# relay_wired.net
KiCad netlist of a schematic drawn in EAGLE
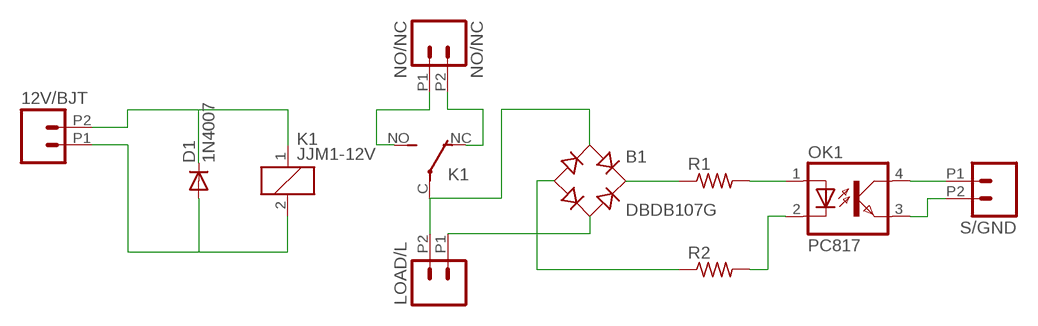
[diagram p0: schematic, sheet 1]

(export (version "E")
  (design (tool "Eeschema 10.0.6"))
  (components
    (comp (ref "12V/BJT")
      (value "M022.54MM_SCREWTERM")
      (footprint "eagle-import:1X02_2.54_SCREWTERM")
      (libsource (lib "eagle-import") (part "M022.54MM_SCREWTERM"))
    )
    (comp (ref "B1")
      (value "DBDB107G")
      (footprint "eagle-import:DB")
      (libsource (lib "eagle-import") (part "DB?GDB107"))
    )
    (comp (ref "D1")
      (value "1N4007")
      (footprint "eagle-import:DO41-10")
      (libsource (lib "eagle-import") (part "1N4004"))
    )
    (comp (ref "K1")
      (value "JJM1-12V")
      (footprint "eagle-import:JJM1C")
      (fields (field (name "MF") "AROMAT/ MATSUSHITA"))
      (libsource (lib "eagle-import") (part "JJM1-12V"))
    )
    (comp (ref "LOAD/L")
      (value "M022.54MM_SCREWTERM")
      (footprint "eagle-import:1X02_2.54_SCREWTERM")
      (libsource (lib "eagle-import") (part "M022.54MM_SCREWTERM"))
    )
    (comp (ref "NO/NC")
      (value "NO/NC")
      (footprint "eagle-import:1X02_2.54_SCREWTERM")
      (libsource (lib "eagle-import") (part "M022.54MM_SCREWTERM"))
    )
    (comp (ref "OK1")
      (value "PC817")
      (footprint "eagle-import:DIL04")
      (fields (field (name "MPN") "PC817X4J000F"))
      (libsource (lib "eagle-import") (part "PC817"))
    )
    (comp (ref "R1")
      (value "R-US_0207/10")
      (footprint "eagle-import:0207_10")
      (libsource (lib "eagle-import") (part "R-US_0207/10"))
    )
    (comp (ref "R2")
      (value "R-US_0207/10")
      (footprint "eagle-import:0207_10")
      (libsource (lib "eagle-import") (part "R-US_0207/10"))
    )
    (comp (ref "S/GND")
      (value "M022.54MM_SCREWTERM")
      (footprint "eagle-import:1X02_2.54_SCREWTERM")
      (libsource (lib "eagle-import") (part "M022.54MM_SCREWTERM"))
    )
  )
  (nets
    (net (code "1") (name "Net-(12V/BJT-1)") (class "Default")
      (node (ref "12V/BJT") (pin "P1") (pinfunction "1_P1") (pintype "passive"))
      (node (ref "D1") (pin "A") (pinfunction "A_A") (pintype "passive"))
      (node (ref "K1") (pin "2") (pinfunction "2_2") (pintype "passive"))
    )
    (net (code "2") (name "Net-(12V/BJT-2)") (class "Default")
      (node (ref "12V/BJT") (pin "P2") (pinfunction "2_P2") (pintype "passive"))
      (node (ref "D1") (pin "C") (pinfunction "C_C") (pintype "passive"))
      (node (ref "K1") (pin "1") (pinfunction "1_1") (pintype "passive"))
    )
    (net (code "3") (name "Net-(B1-Pad+)") (class "Default")
      (node (ref "B1") (pin "+") (pinfunction "+_+") (pintype "passive"))
      (node (ref "R1") (pin "1") (pinfunction "1_1") (pintype "passive"))
    )
    (net (code "4") (name "Net-(B1-Pad-)") (class "Default")
      (node (ref "B1") (pin "-") (pinfunction "-_-") (pintype "passive"))
      (node (ref "R2") (pin "1") (pinfunction "1_1") (pintype "passive"))
    )
    (net (code "5") (name "Net-(K1B-O)") (class "Default")
      (node (ref "K1") (pin "NC") (pinfunction "O_NC") (pintype "passive"))
      (node (ref "NO/NC") (pin "P2") (pinfunction "2_P2") (pintype "passive"))
    )
    (net (code "6") (name "Net-(K1B-P)") (class "Default")
      (node (ref "B1") (pin "AC1") (pinfunction "AC1_AC1") (pintype "passive"))
      (node (ref "K1") (pin "C") (pinfunction "P_C") (pintype "passive"))
      (node (ref "LOAD/L") (pin "P2") (pinfunction "2_P2") (pintype "passive"))
    )
    (net (code "7") (name "Net-(K1B-S)") (class "Default")
      (node (ref "K1") (pin "NO") (pinfunction "S_NO") (pintype "passive"))
      (node (ref "NO/NC") (pin "P1") (pinfunction "1_P1") (pintype "passive"))
    )
    (net (code "8") (name "Net-(LOAD/L-1)") (class "Default")
      (node (ref "B1") (pin "AC2") (pinfunction "AC2_AC2") (pintype "passive"))
      (node (ref "LOAD/L") (pin "P1") (pinfunction "1_P1") (pintype "passive"))
    )
    (net (code "9") (name "Net-(OK1-A)") (class "Default")
      (node (ref "OK1") (pin "1") (pinfunction "A_1") (pintype "passive"))
      (node (ref "R1") (pin "2") (pinfunction "2_2") (pintype "passive"))
    )
    (net (code "10") (name "Net-(OK1-C)") (class "Default")
      (node (ref "OK1") (pin "2") (pinfunction "C_2") (pintype "passive"))
      (node (ref "R2") (pin "2") (pinfunction "2_2") (pintype "passive"))
    )
    (net (code "11") (name "Net-(OK1-COL)") (class "Default")
      (node (ref "OK1") (pin "4") (pinfunction "COL_4") (pintype "passive"))
      (node (ref "S/GND") (pin "P1") (pinfunction "1_P1") (pintype "passive"))
    )
    (net (code "12") (name "Net-(OK1-EMIT)") (class "Default")
      (node (ref "OK1") (pin "3") (pinfunction "EMIT_3") (pintype "passive"))
      (node (ref "S/GND") (pin "P2") (pinfunction "2_P2") (pintype "passive"))
    )
  )
)
